# V40_Test_Adapter.net
KiCad netlist of a schematic drawn in Altium Designer
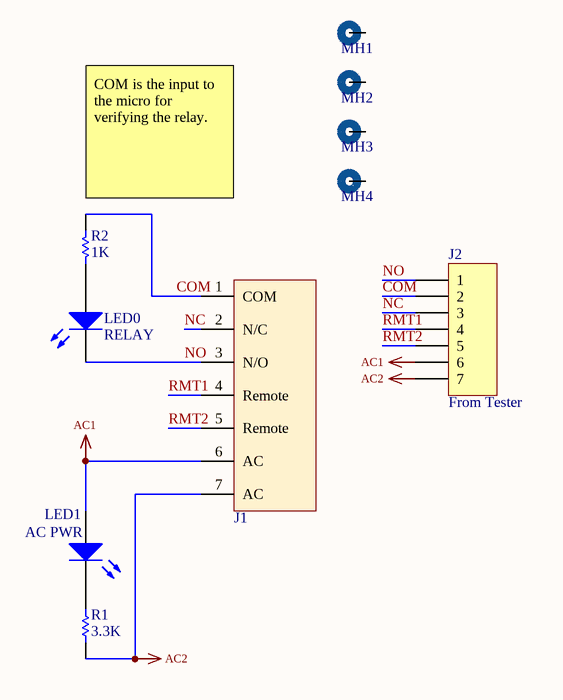
[diagram p0: V40_Test_Adapter.SchDoc]

(export (version "E")
  (design (tool "Eeschema 10.0.6"))
  (components
    (comp (ref "J1")
      (value "Connector")
      (footprint "Phoenix Terminal Block")
      (libsource (lib "V40_Test_Adapter") (part "Connector"))
    )
    (comp (ref "J2")
      (value "From Tester")
      (footprint "HDR1X7")
      (description "Header, 7-Pin")
      (fields (field (name "PUBLISHER") "Altium Limited"))
      (libsource (lib "Miscellaneous Connectors") (part "Header 7"))
    )
    (comp (ref "LED0")
      (value "RELAY")
      (footprint "LED_2")
      (description "Typical INFRARED GaAs LED")
      (fields (field (name "PUBLISHER") "Altium Limited"))
      (libsource (lib "Miscellaneous Devices") (part "LED0"))
    )
    (comp (ref "LED1")
      (value "AC PWR")
      (footprint "LED_2")
      (description "Typical INFRARED GaAs LED")
      (fields (field (name "PUBLISHER") "Altium Limited"))
      (libsource (lib "Miscellaneous Devices") (part "LED0"))
    )
    (comp (ref "MH1")
      (value "Mounting Hole")
      (footprint "Mounting Hole")
      (libsource (lib "V40_Test_Adapter") (part "Mounting Hole"))
    )
    (comp (ref "MH2")
      (value "Mounting Hole")
      (footprint "Mounting Hole")
      (libsource (lib "V40_Test_Adapter") (part "Mounting Hole"))
    )
    (comp (ref "MH3")
      (value "Mounting Hole")
      (footprint "Mounting Hole")
      (libsource (lib "V40_Test_Adapter") (part "Mounting Hole"))
    )
    (comp (ref "MH4")
      (value "Mounting Hole")
      (footprint "Mounting Hole")
      (libsource (lib "V40_Test_Adapter") (part "Mounting Hole"))
    )
    (comp (ref "R1")
      (value "3.3K")
      (footprint "AXIAL-0.3")
      (description "Resistor")
      (fields (field (name "PUBLISHER") "Altium Limited"))
      (libsource (lib "Miscellaneous Devices") (part "Res1"))
    )
    (comp (ref "R2")
      (value "1K")
      (footprint "AXIAL-0.3")
      (description "Resistor")
      (fields (field (name "Comment") "3.3K") (field (name "PUBLISHER") "Altium Limited"))
      (libsource (lib "Miscellaneous Devices") (part "Res1"))
    )
  )
  (nets
    (net (code "1") (name "/COM") (class "Default")
      (node (ref "J1") (pin "1") (pinfunction "COM_1") (pintype "passive"))
      (node (ref "J2") (pin "2") (pinfunction "2_2") (pintype "passive"))
      (node (ref "R2") (pin "2") (pinfunction "2_2") (pintype "passive"))
    )
    (net (code "2") (name "/NC") (class "Default")
      (node (ref "J1") (pin "2") (pinfunction "N/C_2") (pintype "passive"))
      (node (ref "J2") (pin "3") (pinfunction "3_3") (pintype "passive"))
    )
    (net (code "3") (name "/NO") (class "Default")
      (node (ref "J1") (pin "3") (pinfunction "N/O_3") (pintype "passive"))
      (node (ref "J2") (pin "1") (pinfunction "1_1") (pintype "passive"))
      (node (ref "LED0") (pin "2") (pinfunction "K_2") (pintype "passive"))
    )
    (net (code "4") (name "/RMT1") (class "Default")
      (node (ref "J1") (pin "4") (pinfunction "Remote_4") (pintype "passive"))
      (node (ref "J2") (pin "4") (pinfunction "4_4") (pintype "passive"))
    )
    (net (code "5") (name "/RMT2") (class "Default")
      (node (ref "J1") (pin "5") (pinfunction "Remote_5") (pintype "passive"))
      (node (ref "J2") (pin "5") (pinfunction "5_5") (pintype "passive"))
    )
    (net (code "6") (name "AC1") (class "Default")
      (node (ref "J1") (pin "6") (pinfunction "AC_6") (pintype "power_in"))
      (node (ref "J2") (pin "6") (pinfunction "6_6") (pintype "passive"))
      (node (ref "LED1") (pin "1") (pinfunction "A_1") (pintype "passive"))
    )
    (net (code "7") (name "AC2") (class "Default")
      (node (ref "J1") (pin "7") (pinfunction "AC_7") (pintype "power_in"))
      (node (ref "J2") (pin "7") (pinfunction "7_7") (pintype "passive"))
      (node (ref "R1") (pin "2") (pinfunction "2_2") (pintype "passive"))
    )
    (net (code "8") (name "Net-(LED0-A)") (class "Default")
      (node (ref "LED0") (pin "1") (pinfunction "A_1") (pintype "passive"))
      (node (ref "R2") (pin "1") (pinfunction "1_1") (pintype "passive"))
    )
    (net (code "9") (name "Net-(LED1-K)") (class "Default")
      (node (ref "LED1") (pin "2") (pinfunction "K_2") (pintype "passive"))
      (node (ref "R1") (pin "1") (pinfunction "1_1") (pintype "passive"))
    )
    (net (code "10") (name "unconnected-(MH1-Pad0)") (class "Default")
      (node (ref "MH1") (pin "0") (pinfunction "0_0") (pintype "passive"))
    )
    (net (code "11") (name "unconnected-(MH2-Pad0)") (class "Default")
      (node (ref "MH2") (pin "0") (pinfunction "0_0") (pintype "passive"))
    )
    (net (code "12") (name "unconnected-(MH3-Pad0)") (class "Default")
      (node (ref "MH3") (pin "0") (pinfunction "0_0") (pintype "passive"))
    )
    (net (code "13") (name "unconnected-(MH4-Pad0)") (class "Default")
      (node (ref "MH4") (pin "0") (pinfunction "0_0") (pintype "passive"))
    )
  )
)
